# USB3_0.net
KiCad netlist of a schematic drawn in Altium Designer
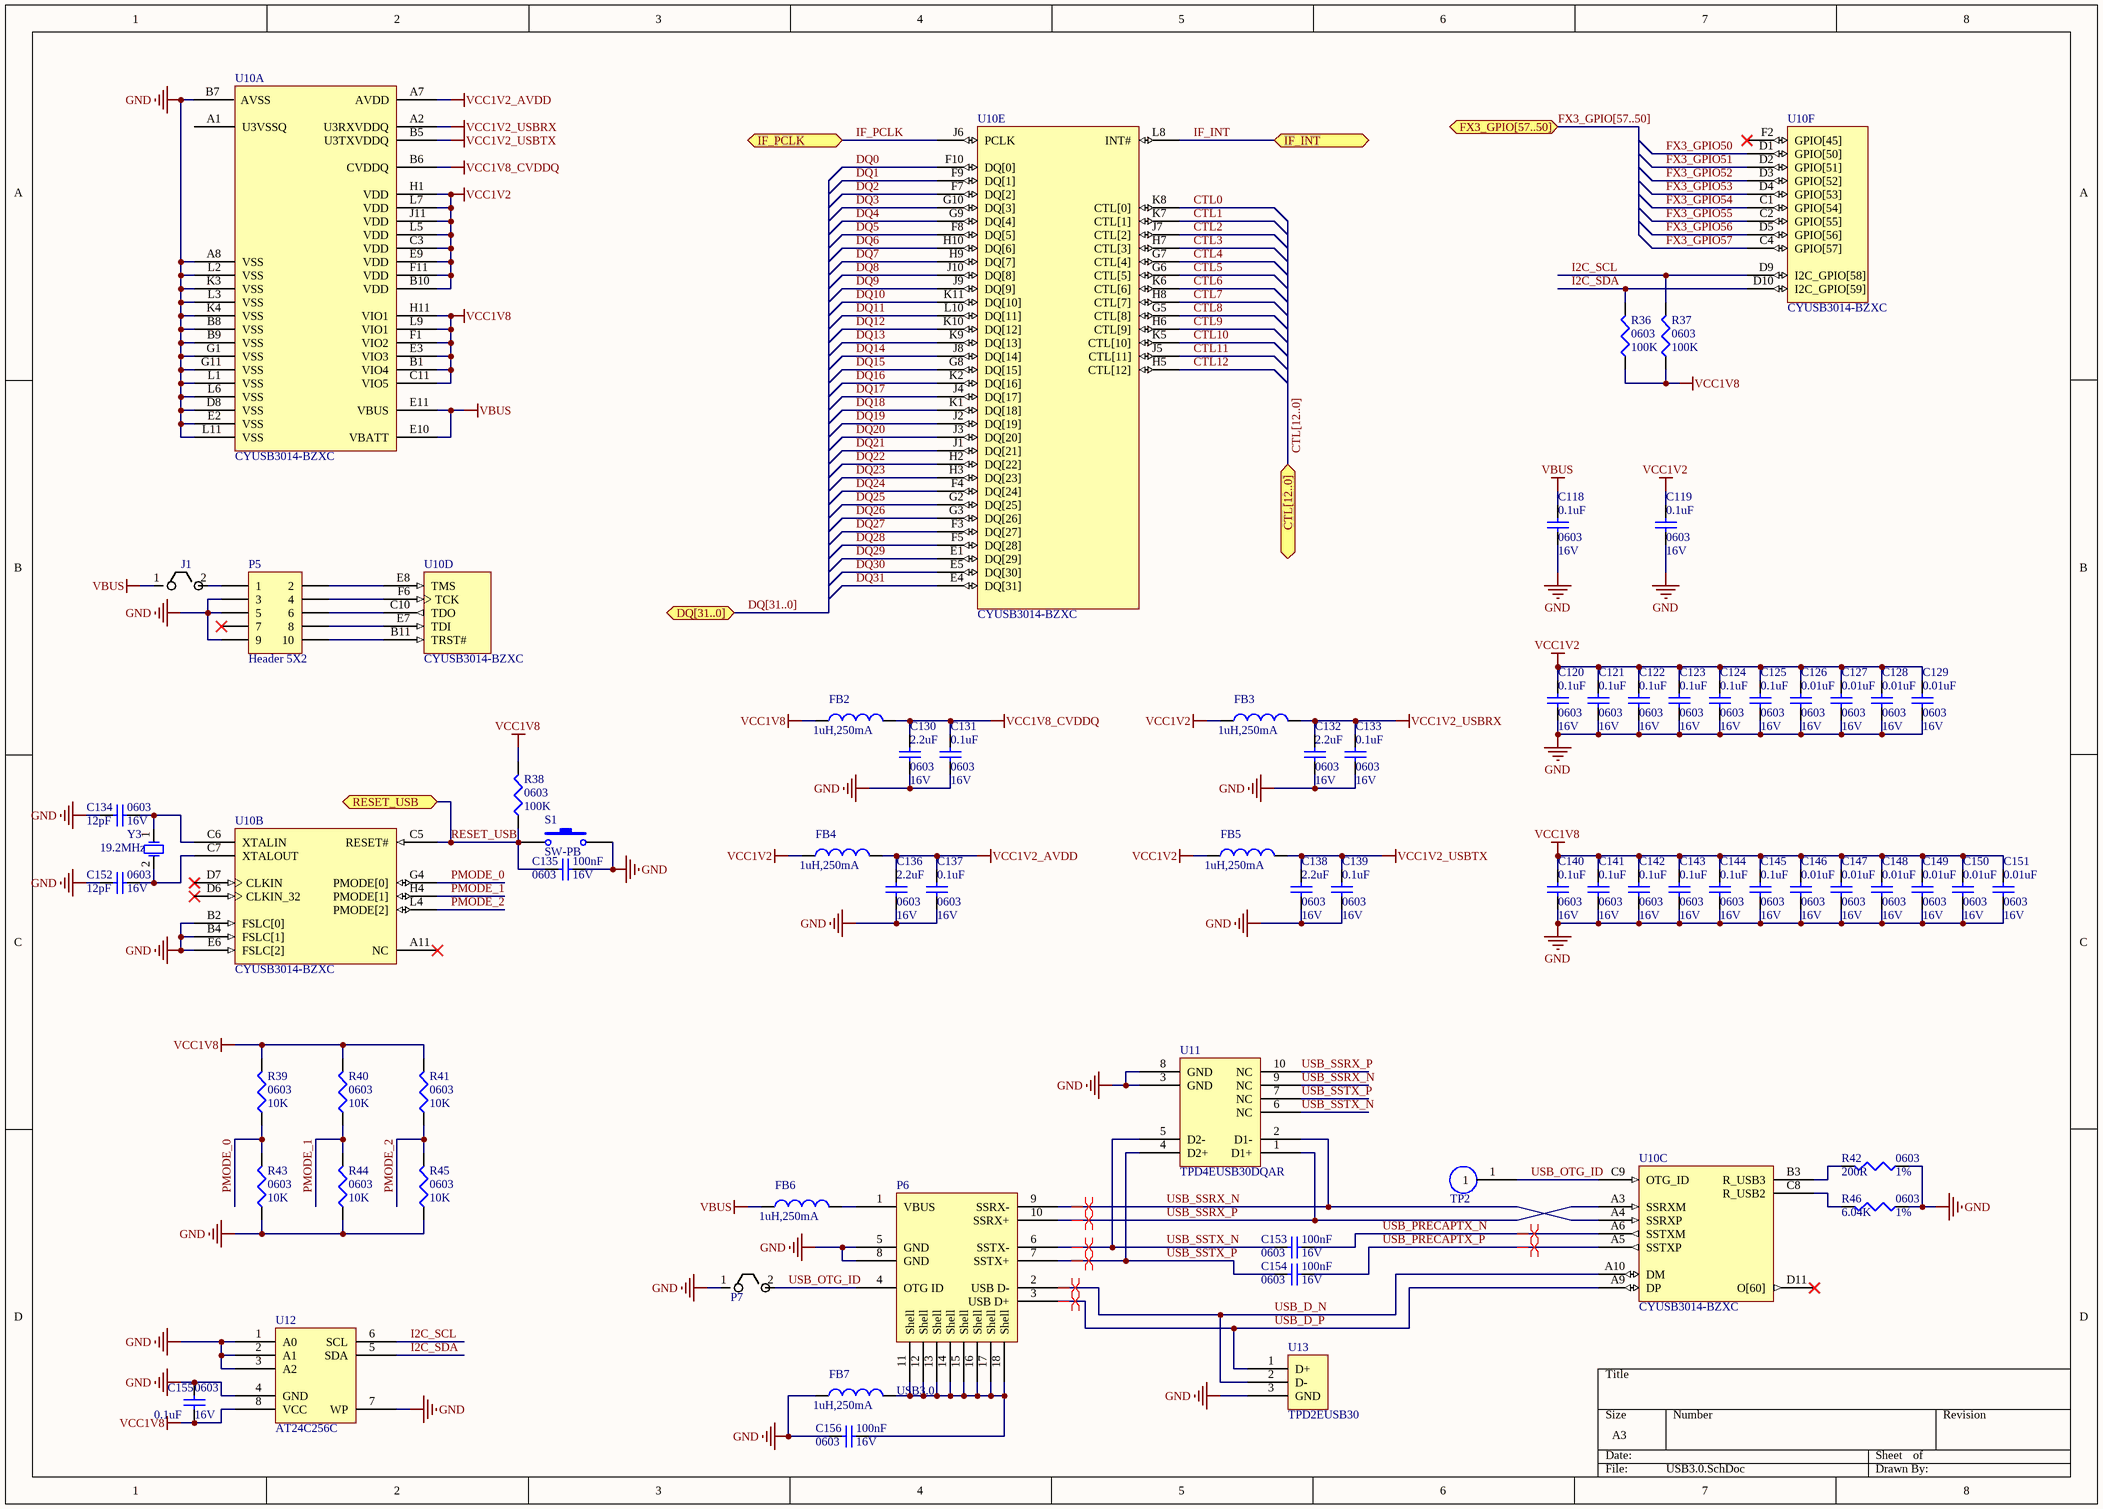
[diagram p0: USB3.0.SchDoc]

(export (version "E")
  (design (tool "Eeschema 10.0.6"))
  (components
    (comp (ref "C118")
      (value "0.1uF")
      (footprint "1608[0603]")
      (description "Capacitor (Semiconductor SIM Model)")
      (fields
        (field (name "PACKAGEREFERENCE") "0603")
        (field (name "V") "16V")
        (field (name "PUBLISHER") "Altium Limited")
      )
      (libsource (lib "Devices") (part "Cap Semi"))
    )
    (comp (ref "C119")
      (value "0.1uF")
      (footprint "1608[0603]")
      (description "Capacitor (Semiconductor SIM Model)")
      (fields
        (field (name "PACKAGEREFERENCE") "0603")
        (field (name "V") "16V")
        (field (name "PUBLISHER") "Altium Limited")
      )
      (libsource (lib "Devices") (part "Cap Semi"))
    )
    (comp (ref "C120")
      (value "0.1uF")
      (footprint "1608[0603]")
      (description "Capacitor (Semiconductor SIM Model)")
      (fields
        (field (name "PACKAGEREFERENCE") "0603")
        (field (name "V") "16V")
        (field (name "PUBLISHER") "Altium Limited")
      )
      (libsource (lib "Devices") (part "Cap Semi"))
    )
    (comp (ref "C121")
      (value "0.1uF")
      (footprint "1608[0603]")
      (description "Capacitor (Semiconductor SIM Model)")
      (fields
        (field (name "PACKAGEREFERENCE") "0603")
        (field (name "V") "16V")
        (field (name "PUBLISHER") "Altium Limited")
      )
      (libsource (lib "Devices") (part "Cap Semi"))
    )
    (comp (ref "C122")
      (value "0.1uF")
      (footprint "1608[0603]")
      (description "Capacitor (Semiconductor SIM Model)")
      (fields
        (field (name "PACKAGEREFERENCE") "0603")
        (field (name "V") "16V")
        (field (name "PUBLISHER") "Altium Limited")
      )
      (libsource (lib "Devices") (part "Cap Semi"))
    )
    (comp (ref "C123")
      (value "0.1uF")
      (footprint "1608[0603]")
      (description "Capacitor (Semiconductor SIM Model)")
      (fields
        (field (name "PACKAGEREFERENCE") "0603")
        (field (name "V") "16V")
        (field (name "PUBLISHER") "Altium Limited")
      )
      (libsource (lib "Devices") (part "Cap Semi"))
    )
    (comp (ref "C124")
      (value "0.1uF")
      (footprint "1608[0603]")
      (description "Capacitor (Semiconductor SIM Model)")
      (fields
        (field (name "PACKAGEREFERENCE") "0603")
        (field (name "V") "16V")
        (field (name "PUBLISHER") "Altium Limited")
      )
      (libsource (lib "Devices") (part "Cap Semi"))
    )
    (comp (ref "C125")
      (value "0.1uF")
      (footprint "1608[0603]")
      (description "Capacitor (Semiconductor SIM Model)")
      (fields
        (field (name "PACKAGEREFERENCE") "0603")
        (field (name "V") "16V")
        (field (name "PUBLISHER") "Altium Limited")
      )
      (libsource (lib "Devices") (part "Cap Semi"))
    )
    (comp (ref "C126")
      (value "0.01uF")
      (footprint "1608[0603]")
      (description "Capacitor (Semiconductor SIM Model)")
      (fields
        (field (name "PACKAGEREFERENCE") "0603")
        (field (name "V") "16V")
        (field (name "PUBLISHER") "Altium Limited")
      )
      (libsource (lib "Devices") (part "Cap Semi"))
    )
    (comp (ref "C127")
      (value "0.01uF")
      (footprint "1608[0603]")
      (description "Capacitor (Semiconductor SIM Model)")
      (fields
        (field (name "PACKAGEREFERENCE") "0603")
        (field (name "V") "16V")
        (field (name "PUBLISHER") "Altium Limited")
      )
      (libsource (lib "Devices") (part "Cap Semi"))
    )
    (comp (ref "C128")
      (value "0.01uF")
      (footprint "1608[0603]")
      (description "Capacitor (Semiconductor SIM Model)")
      (fields
        (field (name "PACKAGEREFERENCE") "0603")
        (field (name "V") "16V")
        (field (name "PUBLISHER") "Altium Limited")
      )
      (libsource (lib "Devices") (part "Cap Semi"))
    )
    (comp (ref "C129")
      (value "0.01uF")
      (footprint "1608[0603]")
      (description "Capacitor (Semiconductor SIM Model)")
      (fields
        (field (name "PACKAGEREFERENCE") "0603")
        (field (name "V") "16V")
        (field (name "PUBLISHER") "Altium Limited")
      )
      (libsource (lib "Devices") (part "Cap Semi"))
    )
    (comp (ref "C130")
      (value "2.2uF")
      (footprint "1608[0603]")
      (description "Capacitor (Semiconductor SIM Model)")
      (fields
        (field (name "PACKAGEREFERENCE") "0603")
        (field (name "V") "16V")
        (field (name "PUBLISHER") "Altium Limited")
      )
      (libsource (lib "Devices") (part "Cap Semi"))
    )
    (comp (ref "C131")
      (value "0.1uF")
      (footprint "1608[0603]")
      (description "Capacitor (Semiconductor SIM Model)")
      (fields
        (field (name "PACKAGEREFERENCE") "0603")
        (field (name "V") "16V")
        (field (name "PUBLISHER") "Altium Limited")
      )
      (libsource (lib "Devices") (part "Cap Semi"))
    )
    (comp (ref "C132")
      (value "2.2uF")
      (footprint "1608[0603]")
      (description "Capacitor (Semiconductor SIM Model)")
      (fields
        (field (name "PACKAGEREFERENCE") "0603")
        (field (name "V") "16V")
        (field (name "PUBLISHER") "Altium Limited")
      )
      (libsource (lib "Devices") (part "Cap Semi"))
    )
    (comp (ref "C133")
      (value "0.1uF")
      (footprint "1608[0603]")
      (description "Capacitor (Semiconductor SIM Model)")
      (fields
        (field (name "PACKAGEREFERENCE") "0603")
        (field (name "V") "16V")
        (field (name "PUBLISHER") "Altium Limited")
      )
      (libsource (lib "Devices") (part "Cap Semi"))
    )
    (comp (ref "C134")
      (value "12pF")
      (footprint "1608[0603]")
      (description "Capacitor (Semiconductor SIM Model)")
      (fields
        (field (name "PACKAGEREFERENCE") "0603")
        (field (name "V") "16V")
        (field (name "PUBLISHER") "Altium Limited")
      )
      (libsource (lib "Devices") (part "Cap Semi"))
    )
    (comp (ref "C135")
      (value "100nF")
      (footprint "1608[0603]")
      (description "Capacitor (Semiconductor SIM Model)")
      (fields
        (field (name "PACKAGEREFERENCE") "0603")
        (field (name "V") "16V")
        (field (name "PUBLISHER") "Altium Limited")
      )
      (libsource (lib "Devices") (part "Cap Semi"))
    )
    (comp (ref "C136")
      (value "2.2uF")
      (footprint "1608[0603]")
      (description "Capacitor (Semiconductor SIM Model)")
      (fields
        (field (name "PACKAGEREFERENCE") "0603")
        (field (name "V") "16V")
        (field (name "PUBLISHER") "Altium Limited")
      )
      (libsource (lib "Devices") (part "Cap Semi"))
    )
    (comp (ref "C137")
      (value "0.1uF")
      (footprint "1608[0603]")
      (description "Capacitor (Semiconductor SIM Model)")
      (fields
        (field (name "PACKAGEREFERENCE") "0603")
        (field (name "V") "16V")
        (field (name "PUBLISHER") "Altium Limited")
      )
      (libsource (lib "Devices") (part "Cap Semi"))
    )
    (comp (ref "C138")
      (value "2.2uF")
      (footprint "1608[0603]")
      (description "Capacitor (Semiconductor SIM Model)")
      (fields
        (field (name "PACKAGEREFERENCE") "0603")
        (field (name "V") "16V")
        (field (name "PUBLISHER") "Altium Limited")
      )
      (libsource (lib "Devices") (part "Cap Semi"))
    )
    (comp (ref "C139")
      (value "0.1uF")
      (footprint "1608[0603]")
      (description "Capacitor (Semiconductor SIM Model)")
      (fields
        (field (name "PACKAGEREFERENCE") "0603")
        (field (name "V") "16V")
        (field (name "PUBLISHER") "Altium Limited")
      )
      (libsource (lib "Devices") (part "Cap Semi"))
    )
    (comp (ref "C140")
      (value "0.1uF")
      (footprint "1608[0603]")
      (description "Capacitor (Semiconductor SIM Model)")
      (fields
        (field (name "PACKAGEREFERENCE") "0603")
        (field (name "V") "16V")
        (field (name "PUBLISHER") "Altium Limited")
      )
      (libsource (lib "Devices") (part "Cap Semi"))
    )
    (comp (ref "C141")
      (value "0.1uF")
      (footprint "1608[0603]")
      (description "Capacitor (Semiconductor SIM Model)")
      (fields
        (field (name "PACKAGEREFERENCE") "0603")
        (field (name "V") "16V")
        (field (name "PUBLISHER") "Altium Limited")
      )
      (libsource (lib "Devices") (part "Cap Semi"))
    )
    (comp (ref "C142")
      (value "0.1uF")
      (footprint "1608[0603]")
      (description "Capacitor (Semiconductor SIM Model)")
      (fields
        (field (name "PACKAGEREFERENCE") "0603")
        (field (name "V") "16V")
        (field (name "PUBLISHER") "Altium Limited")
      )
      (libsource (lib "Devices") (part "Cap Semi"))
    )
    (comp (ref "C143")
      (value "0.1uF")
      (footprint "1608[0603]")
      (description "Capacitor (Semiconductor SIM Model)")
      (fields
        (field (name "PACKAGEREFERENCE") "0603")
        (field (name "V") "16V")
        (field (name "PUBLISHER") "Altium Limited")
      )
      (libsource (lib "Devices") (part "Cap Semi"))
    )
    (comp (ref "C144")
      (value "0.1uF")
      (footprint "1608[0603]")
      (description "Capacitor (Semiconductor SIM Model)")
      (fields
        (field (name "PACKAGEREFERENCE") "0603")
        (field (name "V") "16V")
        (field (name "PUBLISHER") "Altium Limited")
      )
      (libsource (lib "Devices") (part "Cap Semi"))
    )
    (comp (ref "C145")
      (value "0.1uF")
      (footprint "1608[0603]")
      (description "Capacitor (Semiconductor SIM Model)")
      (fields
        (field (name "PACKAGEREFERENCE") "0603")
        (field (name "V") "16V")
        (field (name "PUBLISHER") "Altium Limited")
      )
      (libsource (lib "Devices") (part "Cap Semi"))
    )
    (comp (ref "C146")
      (value "0.01uF")
      (footprint "1608[0603]")
      (description "Capacitor (Semiconductor SIM Model)")
      (fields
        (field (name "PACKAGEREFERENCE") "0603")
        (field (name "V") "16V")
        (field (name "PUBLISHER") "Altium Limited")
      )
      (libsource (lib "Devices") (part "Cap Semi"))
    )
    (comp (ref "C147")
      (value "0.01uF")
      (footprint "1608[0603]")
      (description "Capacitor (Semiconductor SIM Model)")
      (fields
        (field (name "PACKAGEREFERENCE") "0603")
        (field (name "V") "16V")
        (field (name "PUBLISHER") "Altium Limited")
      )
      (libsource (lib "Devices") (part "Cap Semi"))
    )
    (comp (ref "C148")
      (value "0.01uF")
      (footprint "1608[0603]")
      (description "Capacitor (Semiconductor SIM Model)")
      (fields
        (field (name "PACKAGEREFERENCE") "0603")
        (field (name "V") "16V")
        (field (name "PUBLISHER") "Altium Limited")
      )
      (libsource (lib "Devices") (part "Cap Semi"))
    )
    (comp (ref "C149")
      (value "0.01uF")
      (footprint "1608[0603]")
      (description "Capacitor (Semiconductor SIM Model)")
      (fields
        (field (name "PACKAGEREFERENCE") "0603")
        (field (name "V") "16V")
        (field (name "PUBLISHER") "Altium Limited")
      )
      (libsource (lib "Devices") (part "Cap Semi"))
    )
    (comp (ref "C150")
      (value "0.01uF")
      (footprint "1608[0603]")
      (description "Capacitor (Semiconductor SIM Model)")
      (fields
        (field (name "PACKAGEREFERENCE") "0603")
        (field (name "V") "16V")
        (field (name "PUBLISHER") "Altium Limited")
      )
      (libsource (lib "Devices") (part "Cap Semi"))
    )
    (comp (ref "C151")
      (value "0.01uF")
      (footprint "1608[0603]")
      (description "Capacitor (Semiconductor SIM Model)")
      (fields
        (field (name "PACKAGEREFERENCE") "0603")
        (field (name "V") "16V")
        (field (name "PUBLISHER") "Altium Limited")
      )
      (libsource (lib "Devices") (part "Cap Semi"))
    )
    (comp (ref "C152")
      (value "12pF")
      (footprint "1608[0603]")
      (description "Capacitor (Semiconductor SIM Model)")
      (fields
        (field (name "PACKAGEREFERENCE") "0603")
        (field (name "V") "16V")
        (field (name "PUBLISHER") "Altium Limited")
      )
      (libsource (lib "Devices") (part "Cap Semi"))
    )
    (comp (ref "C153")
      (value "100nF")
      (footprint "1608[0603]")
      (description "Capacitor (Semiconductor SIM Model)")
      (fields
        (field (name "PACKAGEREFERENCE") "0603")
        (field (name "V") "16V")
        (field (name "PUBLISHER") "Altium Limited")
      )
      (libsource (lib "Devices") (part "Cap Semi"))
    )
    (comp (ref "C154")
      (value "100nF")
      (footprint "1608[0603]")
      (description "Capacitor (Semiconductor SIM Model)")
      (fields
        (field (name "PACKAGEREFERENCE") "0603")
        (field (name "V") "16V")
        (field (name "PUBLISHER") "Altium Limited")
      )
      (libsource (lib "Devices") (part "Cap Semi"))
    )
    (comp (ref "C155")
      (value "0.1uF")
      (footprint "1608[0603]")
      (description "Capacitor (Semiconductor SIM Model)")
      (fields
        (field (name "PACKAGEREFERENCE") "0603")
        (field (name "V") "16V")
        (field (name "PUBLISHER") "Altium Limited")
      )
      (libsource (lib "Devices") (part "Cap Semi"))
    )
    (comp (ref "C156")
      (value "100nF")
      (footprint "1608[0603]")
      (description "Capacitor (Semiconductor SIM Model)")
      (fields
        (field (name "PACKAGEREFERENCE") "0603")
        (field (name "V") "16V")
        (field (name "PUBLISHER") "Altium Limited")
      )
      (libsource (lib "Devices") (part "Cap Semi"))
    )
    (comp (ref "FB2")
      (value "1uH,250mA")
      (footprint "2012[0805]")
      (description "Inductor")
      (libsource (lib "Miscellaneous Devices") (part "Inductor"))
    )
    (comp (ref "FB3")
      (value "1uH,250mA")
      (footprint "2012[0805]")
      (description "Inductor")
      (libsource (lib "Miscellaneous Devices") (part "Inductor"))
    )
    (comp (ref "FB4")
      (value "1uH,250mA")
      (footprint "2012[0805]")
      (description "Inductor")
      (libsource (lib "Miscellaneous Devices") (part "Inductor"))
    )
    (comp (ref "FB5")
      (value "1uH,250mA")
      (footprint "2012[0805]")
      (description "Inductor")
      (libsource (lib "Miscellaneous Devices") (part "Inductor"))
    )
    (comp (ref "FB6")
      (value "1uH,250mA")
      (footprint "2012[0805]")
      (description "Inductor")
      (libsource (lib "Miscellaneous Devices") (part "Inductor"))
    )
    (comp (ref "FB7")
      (value "1uH,250mA")
      (footprint "2012[0805]")
      (description "Inductor")
      (libsource (lib "Miscellaneous Devices") (part "Inductor"))
    )
    (comp (ref "J1") (value "DNP") (footprint "DNP") (libsource (lib "Spartan6_LX9_A0") (part "DNP")))
    (comp (ref "P5")
      (value "Header 5X2")
      (footprint "HDR2X5")
      (description "Header, 5-Pin, Dual row")
      (fields (field (name "PUBLISHER") "Altium Limited"))
      (libsource (lib "Miscellaneous Connectors") (part "Header 5X2"))
    )
    (comp (ref "P6")
      (value "USB3.0")
      (footprint "ZX360D-B-10P")
      (libsource (lib "Spartan6_LX9_A0") (part "USB3.0"))
    )
    (comp (ref "P7") (value "DNP") (footprint "DNP") (libsource (lib "Spartan6_LX9_A0") (part "DNP")))
    (comp (ref "R36")
      (value "100K")
      (footprint "1608[0603]")
      (description "Resistor")
      (fields
        (field (name "PACKAGEREFERENCE") "0603")
        (field (name "Comment") "Res3")
        (field (name "PUBLISHER") "Altium Limited")
      )
      (libsource (lib "Miscellaneous Devices") (part "Res3"))
    )
    (comp (ref "R37")
      (value "100K")
      (footprint "1608[0603]")
      (description "Resistor")
      (fields
        (field (name "PACKAGEREFERENCE") "0603")
        (field (name "Comment") "Res3")
        (field (name "PUBLISHER") "Altium Limited")
      )
      (libsource (lib "Miscellaneous Devices") (part "Res3"))
    )
    (comp (ref "R38")
      (value "100K")
      (footprint "1608[0603]")
      (description "Resistor")
      (fields
        (field (name "PACKAGEREFERENCE") "0603")
        (field (name "Comment") "Res3")
        (field (name "PUBLISHER") "Altium Limited")
      )
      (libsource (lib "Miscellaneous Devices") (part "Res3"))
    )
    (comp (ref "R39")
      (value "10K")
      (footprint "1608[0603]")
      (description "Resistor")
      (fields
        (field (name "PACKAGEREFERENCE") "0603")
        (field (name "Comment") "Res3")
        (field (name "PUBLISHER") "Altium Limited")
      )
      (libsource (lib "Miscellaneous Devices") (part "Res3"))
    )
    (comp (ref "R40")
      (value "10K")
      (footprint "1608[0603]")
      (description "Resistor")
      (fields
        (field (name "PACKAGEREFERENCE") "0603")
        (field (name "Comment") "Res3")
        (field (name "PUBLISHER") "Altium Limited")
      )
      (libsource (lib "Miscellaneous Devices") (part "Res3"))
    )
    (comp (ref "R41")
      (value "10K")
      (footprint "1608[0603]")
      (description "Resistor")
      (fields
        (field (name "PACKAGEREFERENCE") "0603")
        (field (name "Comment") "Res3")
        (field (name "PUBLISHER") "Altium Limited")
      )
      (libsource (lib "Miscellaneous Devices") (part "Res3"))
    )
    (comp (ref "R42")
      (value "200R")
      (footprint "1608[0603]")
      (description "Resistor")
      (fields
        (field (name "PACKAGEREFERENCE") "0603")
        (field (name "AC") "1%")
        (field (name "Comment") "Res3")
        (field (name "PUBLISHER") "Altium Limited")
      )
      (libsource (lib "Miscellaneous Devices") (part "Res3"))
    )
    (comp (ref "R43")
      (value "10K")
      (footprint "1608[0603]")
      (description "Resistor")
      (fields
        (field (name "PACKAGEREFERENCE") "0603")
        (field (name "Comment") "Res3")
        (field (name "PUBLISHER") "Altium Limited")
      )
      (libsource (lib "Miscellaneous Devices") (part "Res3"))
    )
    (comp (ref "R44")
      (value "10K")
      (footprint "1608[0603]")
      (description "Resistor")
      (fields
        (field (name "PACKAGEREFERENCE") "0603")
        (field (name "Comment") "Res3")
        (field (name "PUBLISHER") "Altium Limited")
      )
      (libsource (lib "Miscellaneous Devices") (part "Res3"))
    )
    (comp (ref "R45")
      (value "10K")
      (footprint "1608[0603]")
      (description "Resistor")
      (fields
        (field (name "PACKAGEREFERENCE") "0603")
        (field (name "Comment") "Res3")
        (field (name "PUBLISHER") "Altium Limited")
      )
      (libsource (lib "Miscellaneous Devices") (part "Res3"))
    )
    (comp (ref "R46")
      (value "6.04K")
      (footprint "1608[0603]")
      (description "Resistor")
      (fields
        (field (name "PACKAGEREFERENCE") "0603")
        (field (name "AC") "1%")
        (field (name "Comment") "Res3")
        (field (name "PUBLISHER") "Altium Limited")
      )
      (libsource (lib "Miscellaneous Devices") (part "Res3"))
    )
    (comp (ref "S1")
      (value "SW-PB")
      (footprint "SPST-2")
      (description "Switch")
      (fields (field (name "PUBLISHER") "Altium Limited"))
      (libsource (lib "Miscellaneous Devices") (part "SW-PB"))
    )
    (comp (ref "TP2") (value "TP") (libsource (lib "Spartan6_LX9_A0") (part "TP")))
    (comp (ref "U10")
      (value "CYUSB3014-BZXC")
      (footprint "CYUSB3014")
      (libsource (lib "Spartan6_LX9_A0") (part "CYUSB3014-BZXC"))
    )
    (comp (ref "U11")
      (value "TPD4EUSB30DQAR")
      (footprint "TPD4EUSB30")
      (description "4-Channel ESD Protection for Super-Speed USB 3.0 Interface")
      (libsource (lib "Spartan6_LX9_A0") (part "TPD4EUSB30DQAR"))
    )
    (comp (ref "U12")
      (value "AT24C256C")
      (footprint "AT24C256C[SOP8]")
      (libsource (lib "Spartan6_LX9_A0") (part "AT24C256C"))
    )
    (comp (ref "U13")
      (value "TPD2EUSB30")
      (footprint "TPE2USB30")
      (libsource (lib "Spartan6_LX9_A0") (part "TPD2EUSB30"))
    )
    (comp (ref "Y3")
      (value "19.2MHz")
      (footprint "XTAL_A")
      (description "Crystal Oscillator")
      (fields (field (name "PUBLISHER") "Altium Limited"))
      (libsource (lib "Devices") (part "XTAL"))
    )
  )
  (nets
    (net (code "1") (name "/CTL0") (class "Default")
      (node (ref "U10") (pin "K8") (pinfunction "CTL[0]_K8") (pintype "bidirectional"))
    )
    (net (code "2") (name "/CTL1") (class "Default")
      (node (ref "U10") (pin "K7") (pinfunction "CTL[1]_K7") (pintype "bidirectional"))
    )
    (net (code "3") (name "/CTL2") (class "Default")
      (node (ref "U10") (pin "J7") (pinfunction "CTL[2]_J7") (pintype "bidirectional"))
    )
    (net (code "4") (name "/CTL3") (class "Default")
      (node (ref "U10") (pin "H7") (pinfunction "CTL[3]_H7") (pintype "bidirectional"))
    )
    (net (code "5") (name "/CTL4") (class "Default")
      (node (ref "U10") (pin "G7") (pinfunction "CTL[4]_G7") (pintype "bidirectional"))
    )
    (net (code "6") (name "/CTL5") (class "Default")
      (node (ref "U10") (pin "G6") (pinfunction "CTL[5]_G6") (pintype "bidirectional"))
    )
    (net (code "7") (name "/CTL6") (class "Default")
      (node (ref "U10") (pin "K6") (pinfunction "CTL[6]_K6") (pintype "bidirectional"))
    )
    (net (code "8") (name "/CTL7") (class "Default")
      (node (ref "U10") (pin "H8") (pinfunction "CTL[7]_H8") (pintype "bidirectional"))
    )
    (net (code "9") (name "/CTL8") (class "Default")
      (node (ref "U10") (pin "G5") (pinfunction "CTL[8]_G5") (pintype "bidirectional"))
    )
    (net (code "10") (name "/CTL9") (class "Default")
      (node (ref "U10") (pin "H6") (pinfunction "CTL[9]_H6") (pintype "bidirectional"))
    )
    (net (code "11") (name "/CTL10") (class "Default")
      (node (ref "U10") (pin "K5") (pinfunction "CTL[10]_K5") (pintype "bidirectional"))
    )
    (net (code "12") (name "/CTL11") (class "Default")
      (node (ref "U10") (pin "J5") (pinfunction "CTL[11]_J5") (pintype "bidirectional"))
    )
    (net (code "13") (name "/CTL12") (class "Default")
      (node (ref "U10") (pin "H5") (pinfunction "CTL[12]_H5") (pintype "bidirectional"))
    )
    (net (code "15") (name "/DQ0") (class "Default")
      (node (ref "U10") (pin "F10") (pinfunction "DQ[0]_F10") (pintype "bidirectional"))
    )
    (net (code "16") (name "/DQ1") (class "Default")
      (node (ref "U10") (pin "F9") (pinfunction "DQ[1]_F9") (pintype "bidirectional"))
    )
    (net (code "17") (name "/DQ2") (class "Default")
      (node (ref "U10") (pin "F7") (pinfunction "DQ[2]_F7") (pintype "bidirectional"))
    )
    (net (code "18") (name "/DQ3") (class "Default")
      (node (ref "U10") (pin "G10") (pinfunction "DQ[3]_G10") (pintype "bidirectional"))
    )
    (net (code "19") (name "/DQ4") (class "Default")
      (node (ref "U10") (pin "G9") (pinfunction "DQ[4]_G9") (pintype "bidirectional"))
    )
    (net (code "20") (name "/DQ5") (class "Default")
      (node (ref "U10") (pin "F8") (pinfunction "DQ[5]_F8") (pintype "bidirectional"))
    )
    (net (code "21") (name "/DQ6") (class "Default")
      (node (ref "U10") (pin "H10") (pinfunction "DQ[6]_H10") (pintype "bidirectional"))
    )
    (net (code "22") (name "/DQ7") (class "Default")
      (node (ref "U10") (pin "H9") (pinfunction "DQ[7]_H9") (pintype "bidirectional"))
    )
    (net (code "23") (name "/DQ8") (class "Default")
      (node (ref "U10") (pin "J10") (pinfunction "DQ[8]_J10") (pintype "bidirectional"))
    )
    (net (code "24") (name "/DQ9") (class "Default")
      (node (ref "U10") (pin "J9") (pinfunction "DQ[9]_J9") (pintype "bidirectional"))
    )
    (net (code "25") (name "/DQ10") (class "Default")
      (node (ref "U10") (pin "K11") (pinfunction "DQ[10]_K11") (pintype "bidirectional"))
    )
    (net (code "26") (name "/DQ11") (class "Default")
      (node (ref "U10") (pin "L10") (pinfunction "DQ[11]_L10") (pintype "bidirectional"))
    )
    (net (code "27") (name "/DQ12") (class "Default")
      (node (ref "U10") (pin "K10") (pinfunction "DQ[12]_K10") (pintype "bidirectional"))
    )
    (net (code "28") (name "/DQ13") (class "Default")
      (node (ref "U10") (pin "K9") (pinfunction "DQ[13]_K9") (pintype "bidirectional"))
    )
    (net (code "29") (name "/DQ14") (class "Default")
      (node (ref "U10") (pin "J8") (pinfunction "DQ[14]_J8") (pintype "bidirectional"))
    )
    (net (code "30") (name "/DQ15") (class "Default")
      (node (ref "U10") (pin "G8") (pinfunction "DQ[15]_G8") (pintype "bidirectional"))
    )
    (net (code "31") (name "/DQ16") (class "Default")
      (node (ref "U10") (pin "K2") (pinfunction "DQ[16]_K2") (pintype "bidirectional"))
    )
    (net (code "32") (name "/DQ17") (class "Default")
      (node (ref "U10") (pin "J4") (pinfunction "DQ[17]_J4") (pintype "bidirectional"))
    )
    (net (code "33") (name "/DQ18") (class "Default")
      (node (ref "U10") (pin "K1") (pinfunction "DQ[18]_K1") (pintype "bidirectional"))
    )
    (net (code "34") (name "/DQ19") (class "Default")
      (node (ref "U10") (pin "J2") (pinfunction "DQ[19]_J2") (pintype "bidirectional"))
    )
    (net (code "35") (name "/DQ20") (class "Default")
      (node (ref "U10") (pin "J3") (pinfunction "DQ[20]_J3") (pintype "bidirectional"))
    )
    (net (code "36") (name "/DQ21") (class "Default")
      (node (ref "U10") (pin "J1") (pinfunction "DQ[21]_J1") (pintype "bidirectional"))
    )
    (net (code "37") (name "/DQ22") (class "Default")
      (node (ref "U10") (pin "H2") (pinfunction "DQ[22]_H2") (pintype "bidirectional"))
    )
    (net (code "38") (name "/DQ23") (class "Default")
      (node (ref "U10") (pin "H3") (pinfunction "DQ[23]_H3") (pintype "bidirectional"))
    )
    (net (code "39") (name "/DQ24") (class "Default")
      (node (ref "U10") (pin "F4") (pinfunction "DQ[24]_F4") (pintype "bidirectional"))
    )
    (net (code "40") (name "/DQ25") (class "Default")
      (node (ref "U10") (pin "G2") (pinfunction "DQ[25]_G2") (pintype "bidirectional"))
    )
    (net (code "41") (name "/DQ26") (class "Default")
      (node (ref "U10") (pin "G3") (pinfunction "DQ[26]_G3") (pintype "bidirectional"))
    )
    (net (code "42") (name "/DQ27") (class "Default")
      (node (ref "U10") (pin "F3") (pinfunction "DQ[27]_F3") (pintype "bidirectional"))
    )
    (net (code "43") (name "/DQ28") (class "Default")
      (node (ref "U10") (pin "F5") (pinfunction "DQ[28]_F5") (pintype "bidirectional"))
    )
    (net (code "44") (name "/DQ29") (class "Default")
      (node (ref "U10") (pin "E1") (pinfunction "DQ[29]_E1") (pintype "bidirectional"))
    )
    (net (code "45") (name "/DQ30") (class "Default")
      (node (ref "U10") (pin "E5") (pinfunction "DQ[30]_E5") (pintype "bidirectional"))
    )
    (net (code "46") (name "/DQ31") (class "Default")
      (node (ref "U10") (pin "E4") (pinfunction "DQ[31]_E4") (pintype "bidirectional"))
    )
    (net (code "48") (name "/FX3_GPIO50") (class "Default")
      (node (ref "U10") (pin "D1") (pinfunction "GPIO[50]_D1") (pintype "bidirectional"))
    )
    (net (code "49") (name "/FX3_GPIO51") (class "Default")
      (node (ref "U10") (pin "D2") (pinfunction "GPIO[51]_D2") (pintype "bidirectional"))
    )
    (net (code "50") (name "/FX3_GPIO52") (class "Default")
      (node (ref "U10") (pin "D3") (pinfunction "GPIO[52]_D3") (pintype "bidirectional"))
    )
    (net (code "51") (name "/FX3_GPIO53") (class "Default")
      (node (ref "U10") (pin "D4") (pinfunction "GPIO[53]_D4") (pintype "bidirectional"))
    )
    (net (code "52") (name "/FX3_GPIO54") (class "Default")
      (node (ref "U10") (pin "C1") (pinfunction "GPIO[54]_C1") (pintype "bidirectional"))
    )
    (net (code "53") (name "/FX3_GPIO55") (class "Default")
      (node (ref "U10") (pin "C2") (pinfunction "GPIO[55]_C2") (pintype "bidirectional"))
    )
    (net (code "54") (name "/FX3_GPIO56") (class "Default")
      (node (ref "U10") (pin "D5") (pinfunction "GPIO[56]_D5") (pintype "bidirectional"))
    )
    (net (code "55") (name "/FX3_GPIO57") (class "Default")
      (node (ref "U10") (pin "C4") (pinfunction "GPIO[57]_C4") (pintype "bidirectional"))
    )
    (net (code "57") (name "/I2C_SCL") (class "Default")
      (node (ref "R37") (pin "2") (pinfunction "2_2") (pintype "passive"))
      (node (ref "U10") (pin "D9") (pinfunction "I2C_GPIO[58]_D9") (pintype "bidirectional"))
      (node (ref "U12") (pin "6") (pinfunction "SCL_6") (pintype "passive"))
    )
    (net (code "58") (name "/I2C_SDA") (class "Default")
      (node (ref "R36") (pin "2") (pinfunction "2_2") (pintype "passive"))
      (node (ref "U10") (pin "D10") (pinfunction "I2C_GPIO[59]_D10") (pintype "bidirectional"))
      (node (ref "U12") (pin "5") (pinfunction "SDA_5") (pintype "passive"))
    )
    (net (code "59") (name "/IF_INT") (class "Default")
      (node (ref "U10") (pin "L8") (pinfunction "INT#_L8") (pintype "bidirectional"))
    )
    (net (code "60") (name "/IF_PCLK") (class "Default")
      (node (ref "U10") (pin "J6") (pinfunction "PCLK_J6") (pintype "bidirectional"))
    )
    (net (code "61") (name "/PMODE_0") (class "Default")
      (node (ref "R39") (pin "1") (pinfunction "1_1") (pintype "passive"))
      (node (ref "R43") (pin "2") (pinfunction "2_2") (pintype "passive"))
      (node (ref "U10") (pin "G4") (pinfunction "PMODE[0]_G4") (pintype "bidirectional"))
    )
    (net (code "62") (name "/PMODE_1") (class "Default")
      (node (ref "R40") (pin "1") (pinfunction "1_1") (pintype "passive"))
      (node (ref "R44") (pin "2") (pinfunction "2_2") (pintype "passive"))
      (node (ref "U10") (pin "H4") (pinfunction "PMODE[1]_H4") (pintype "bidirectional"))
    )
    (net (code "63") (name "/PMODE_2") (class "Default")
      (node (ref "R41") (pin "1") (pinfunction "1_1") (pintype "passive"))
      (node (ref "R45") (pin "2") (pinfunction "2_2") (pintype "passive"))
      (node (ref "U10") (pin "L4") (pinfunction "PMODE[2]_L4") (pintype "bidirectional"))
    )
    (net (code "64") (name "/RESET_USB") (class "Default")
      (node (ref "C135") (pin "1") (pinfunction "1_1") (pintype "passive"))
      (node (ref "R38") (pin "1") (pinfunction "1_1") (pintype "passive"))
      (node (ref "S1") (pin "1") (pinfunction "1_1") (pintype "passive"))
      (node (ref "U10") (pin "C5") (pinfunction "RESET#_C5") (pintype "input"))
    )
    (net (code "65") (name "/USB_D_N") (class "Default")
      (node (ref "P6") (pin "2") (pinfunction "USB_D-_2") (pintype "passive"))
      (node (ref "U10") (pin "A10") (pinfunction "DM_A10") (pintype "bidirectional"))
      (node (ref "U13") (pin "2") (pinfunction "D-_2") (pintype "passive"))
    )
    (net (code "66") (name "/USB_D_P") (class "Default")
      (node (ref "P6") (pin "3") (pinfunction "USB_D+_3") (pintype "passive"))
      (node (ref "U10") (pin "A9") (pinfunction "DP_A9") (pintype "bidirectional"))
      (node (ref "U13") (pin "1") (pinfunction "D+_1") (pintype "passive"))
    )
    (net (code "67") (name "/USB_OTG_ID") (class "Default")
      (node (ref "P6") (pin "4") (pinfunction "OTG_ID_4") (pintype "passive"))
      (node (ref "P7") (pin "2") (pinfunction "2_2") (pintype "passive"))
      (node (ref "TP2") (pin "1") (pinfunction "1_1") (pintype "passive"))
      (node (ref "U10") (pin "C9") (pinfunction "OTG_ID_C9") (pintype "input"))
    )
    (net (code "68") (name "/USB_PRECAPTX_N") (class "Default")
      (node (ref "C153") (pin "2") (pinfunction "2_2") (pintype "passive"))
      (node (ref "U10") (pin "A6") (pinfunction "SSTXM_A6") (pintype "output"))
    )
    (net (code "69") (name "/USB_PRECAPTX_P") (class "Default")
      (node (ref "C154") (pin "2") (pinfunction "2_2") (pintype "passive"))
      (node (ref "U10") (pin "A5") (pinfunction "SSTXP_A5") (pintype "output"))
    )
    (net (code "70") (name "/USB_SSRX_N") (class "Default")
      (node (ref "P6") (pin "9") (pinfunction "SSRX-_9") (pintype "passive"))
      (node (ref "U10") (pin "A4") (pinfunction "SSRXP_A4") (pintype "input"))
      (node (ref "U11") (pin "2") (pinfunction "D1-_2") (pintype "passive"))
      (node (ref "U11") (pin "9") (pinfunction "NC_9") (pintype "passive"))
    )
    (net (code "71") (name "/USB_SSRX_P") (class "Default")
      (node (ref "P6") (pin "10") (pinfunction "SSRX+_10") (pintype "passive"))
      (node (ref "U10") (pin "A3") (pinfunction "SSRXM_A3") (pintype "input"))
      (node (ref "U11") (pin "1") (pinfunction "D1+_1") (pintype "passive"))
      (node (ref "U11") (pin "10") (pinfunction "NC_10") (pintype "passive"))
    )
    (net (code "72") (name "/USB_SSTX_N") (class "Default")
      (node (ref "C153") (pin "1") (pinfunction "1_1") (pintype "passive"))
      (node (ref "P6") (pin "6") (pinfunction "SSTX-_6") (pintype "passive"))
      (node (ref "U11") (pin "5") (pinfunction "D2-_5") (pintype "passive"))
      (node (ref "U11") (pin "6") (pinfunction "NC_6") (pintype "passive"))
    )
    (net (code "73") (name "/USB_SSTX_P") (class "Default")
      (node (ref "C154") (pin "1") (pinfunction "1_1") (pintype "passive"))
      (node (ref "P6") (pin "7") (pinfunction "SSTX+_7") (pintype "passive"))
      (node (ref "U11") (pin "4") (pinfunction "D2+_4") (pintype "passive"))
      (node (ref "U11") (pin "7") (pinfunction "NC_7") (pintype "passive"))
    )
    (net (code "74") (name "GND") (class "Default")
      (node (ref "C118") (pin "2") (pinfunction "2_2") (pintype "passive"))
      (node (ref "C119") (pin "2") (pinfunction "2_2") (pintype "passive"))
      (node (ref "C120") (pin "2") (pinfunction "2_2") (pintype "passive"))
      (node (ref "C121") (pin "2") (pinfunction "2_2") (pintype "passive"))
      (node (ref "C122") (pin "2") (pinfunction "2_2") (pintype "passive"))
      (node (ref "C123") (pin "2") (pinfunction "2_2") (pintype "passive"))
      (node (ref "C124") (pin "2") (pinfunction "2_2") (pintype "passive"))
      (node (ref "C125") (pin "2") (pinfunction "2_2") (pintype "passive"))
      (node (ref "C126") (pin "2") (pinfunction "2_2") (pintype "passive"))
      (node (ref "C127") (pin "2") (pinfunction "2_2") (pintype "passive"))
      (node (ref "C128") (pin "2") (pinfunction "2_2") (pintype "passive"))
      (node (ref "C129") (pin "2") (pinfunction "2_2") (pintype "passive"))
      (node (ref "C130") (pin "2") (pinfunction "2_2") (pintype "passive"))
      (node (ref "C131") (pin "2") (pinfunction "2_2") (pintype "passive"))
      (node (ref "C132") (pin "2") (pinfunction "2_2") (pintype "passive"))
      (node (ref "C133") (pin "2") (pinfunction "2_2") (pintype "passive"))
      (node (ref "C134") (pin "2") (pinfunction "2_2") (pintype "passive"))
      (node (ref "C135") (pin "2") (pinfunction "2_2") (pintype "passive"))
      (node (ref "C136") (pin "2") (pinfunction "2_2") (pintype "passive"))
      (node (ref "C137") (pin "2") (pinfunction "2_2") (pintype "passive"))
      (node (ref "C138") (pin "2") (pinfunction "2_2") (pintype "passive"))
      (node (ref "C139") (pin "2") (pinfunction "2_2") (pintype "passive"))
      (node (ref "C140") (pin "2") (pinfunction "2_2") (pintype "passive"))
      (node (ref "C141") (pin "2") (pinfunction "2_2") (pintype "passive"))
      (node (ref "C142") (pin "2") (pinfunction "2_2") (pintype "passive"))
      (node (ref "C143") (pin "2") (pinfunction "2_2") (pintype "passive"))
      (node (ref "C144") (pin "2") (pinfunction "2_2") (pintype "passive"))
      (node (ref "C145") (pin "2") (pinfunction "2_2") (pintype "passive"))
      (node (ref "C146") (pin "2") (pinfunction "2_2") (pintype "passive"))
      (node (ref "C147") (pin "2") (pinfunction "2_2") (pintype "passive"))
      (node (ref "C148") (pin "2") (pinfunction "2_2") (pintype "passive"))
      (node (ref "C149") (pin "2") (pinfunction "2_2") (pintype "passive"))
      (node (ref "C150") (pin "2") (pinfunction "2_2") (pintype "passive"))
      (node (ref "C151") (pin "2") (pinfunction "2_2") (pintype "passive"))
      (node (ref "C152") (pin "2") (pinfunction "2_2") (pintype "passive"))
      (node (ref "C155") (pin "2") (pinfunction "2_2") (pintype "passive"))
      (node (ref "C156") (pin "1") (pinfunction "1_1") (pintype "passive"))
      (node (ref "FB7") (pin "1") (pinfunction "1_1") (pintype "passive"))
      (node (ref "P5") (pin "3") (pinfunction "3_3") (pintype "passive"))
      (node (ref "P5") (pin "5") (pinfunction "5_5") (pintype "passive"))
      (node (ref "P5") (pin "9") (pinfunction "9_9") (pintype "passive"))
      (node (ref "P6") (pin "5") (pinfunction "GND_5") (pintype "passive"))
      (node (ref "P6") (pin "8") (pinfunction "GND_8") (pintype "passive"))
      (node (ref "P7") (pin "1") (pinfunction "1_1") (pintype "passive"))
      (node (ref "R42") (pin "1") (pinfunction "1_1") (pintype "passive"))
      (node (ref "R43") (pin "1") (pinfunction "1_1") (pintype "passive"))
      (node (ref "R44") (pin "1") (pinfunction "1_1") (pintype "passive"))
      (node (ref "R45") (pin "1") (pinfunction "1_1") (pintype "passive"))
      (node (ref "R46") (pin "1") (pinfunction "1_1") (pintype "passive"))
      (node (ref "S1") (pin "2") (pinfunction "2_2") (pintype "passive"))
      (node (ref "U10") (pin "A8") (pinfunction "VSS_A8") (pintype "power_in"))
      (node (ref "U10") (pin "B2") (pinfunction "FSLC[0]_B2") (pintype "input"))
      (node (ref "U10") (pin "B4") (pinfunction "FSLC[1]_B4") (pintype "input"))
      (node (ref "U10") (pin "B7") (pinfunction "AVSS_B7") (pintype "power_in"))
      (node (ref "U10") (pin "B8") (pinfunction "VSS_B8") (pintype "power_in"))
      (node (ref "U10") (pin "B9") (pinfunction "VSS_B9") (pintype "power_in"))
      (node (ref "U10") (pin "D8") (pinfunction "VSS_D8") (pintype "power_in"))
      (node (ref "U10") (pin "E2") (pinfunction "VSS_E2") (pintype "power_in"))
      (node (ref "U10") (pin "E6") (pinfunction "FSLC[2]_E6") (pintype "input"))
      (node (ref "U10") (pin "G1") (pinfunction "VSS_G1") (pintype "power_in"))
      (node (ref "U10") (pin "G11") (pinfunction "VSS_G11") (pintype "power_in"))
      (node (ref "U10") (pin "K3") (pinfunction "VSS_K3") (pintype "power_in"))
      (node (ref "U10") (pin "K4") (pinfunction "VSS_K4") (pintype "power_in"))
      (node (ref "U10") (pin "L1") (pinfunction "VSS_L1") (pintype "power_in"))
      (node (ref "U10") (pin "L11") (pinfunction "VSS_L11") (pintype "power_in"))
      (node (ref "U10") (pin "L2") (pinfunction "VSS_L2") (pintype "power_in"))
      (node (ref "U10") (pin "L3") (pinfunction "VSS_L3") (pintype "power_in"))
      (node (ref "U10") (pin "L6") (pinfunction "VSS_L6") (pintype "power_in"))
      (node (ref "U11") (pin "3") (pinfunction "GND_3") (pintype "passive"))
      (node (ref "U11") (pin "8") (pinfunction "GND_8") (pintype "passive"))
      (node (ref "U12") (pin "1") (pinfunction "A0_1") (pintype "passive"))
      (node (ref "U12") (pin "2") (pinfunction "A1_2") (pintype "passive"))
      (node (ref "U12") (pin "3") (pinfunction "A2_3") (pintype "passive"))
      (node (ref "U12") (pin "4") (pinfunction "GND_4") (pintype "passive"))
      (node (ref "U12") (pin "7") (pinfunction "WP_7") (pintype "passive"))
      (node (ref "U13") (pin "3") (pinfunction "GND_3") (pintype "passive"))
    )
    (net (code "75") (name "Net-(C156-Pad2)") (class "Default")
      (node (ref "C156") (pin "2") (pinfunction "2_2") (pintype "passive"))
      (node (ref "FB7") (pin "2") (pinfunction "2_2") (pintype "passive"))
      (node (ref "P6") (pin "11") (pinfunction "Shell_11") (pintype "passive"))
      (node (ref "P6") (pin "12") (pinfunction "Shell_12") (pintype "passive"))
      (node (ref "P6") (pin "13") (pinfunction "Shell_13") (pintype "passive"))
      (node (ref "P6") (pin "14") (pinfunction "Shell_14") (pintype "passive"))
      (node (ref "P6") (pin "15") (pinfunction "Shell_15") (pintype "passive"))
      (node (ref "P6") (pin "16") (pinfunction "Shell_16") (pintype "passive"))
      (node (ref "P6") (pin "17") (pinfunction "Shell_17") (pintype "passive"))
      (node (ref "P6") (pin "18") (pinfunction "Shell_18") (pintype "passive"))
    )
    (net (code "76") (name "Net-(J1-Pad2)") (class "Default")
      (node (ref "J1") (pin "2") (pinfunction "2_2") (pintype "passive"))
      (node (ref "P5") (pin "1") (pinfunction "1_1") (pintype "passive"))
    )
    (net (code "77") (name "Net-(P6-VBUS)") (class "Default")
      (node (ref "FB6") (pin "2") (pinfunction "2_2") (pintype "passive"))
      (node (ref "P6") (pin "1") (pinfunction "VBUS_1") (pintype "passive"))
    )
    (net (code "78") (name "Net-(U10B-XTALIN)") (class "Default")
      (node (ref "C134") (pin "1") (pinfunction "1_1") (pintype "passive"))
      (node (ref "U10") (pin "C6") (pinfunction "XTALIN_C6") (pintype "passive"))
      (node (ref "Y3") (pin "1") (pinfunction "OSC1_1") (pintype "passive"))
    )
    (net (code "79") (name "Net-(U10B-XTALOUT)") (class "Default")
      (node (ref "C152") (pin "1") (pinfunction "1_1") (pintype "passive"))
      (node (ref "U10") (pin "C7") (pinfunction "XTALOUT_C7") (pintype "passive"))
      (node (ref "Y3") (pin "2") (pinfunction "OSC2_2") (pintype "passive"))
    )
    (net (code "80") (name "Net-(U10C-R_USB2)") (class "Default")
      (node (ref "R46") (pin "2") (pinfunction "2_2") (pintype "passive"))
      (node (ref "U10") (pin "C8") (pinfunction "R_USB2_C8") (pintype "passive"))
    )
    (net (code "81") (name "Net-(U10C-R_USB3)") (class "Default")
      (node (ref "R42") (pin "2") (pinfunction "2_2") (pintype "passive"))
      (node (ref "U10") (pin "B3") (pinfunction "R_USB3_B3") (pintype "passive"))
    )
    (net (code "82") (name "Net-(U10D-TCK)") (class "Default")
      (node (ref "P5") (pin "4") (pinfunction "4_4") (pintype "passive"))
      (node (ref "U10") (pin "F6") (pinfunction "TCK_F6") (pintype "input"))
    )
    (net (code "83") (name "Net-(U10D-TDI)") (class "Default")
      (node (ref "P5") (pin "8") (pinfunction "8_8") (pintype "passive"))
      (node (ref "U10") (pin "E7") (pinfunction "TDI_E7") (pintype "input"))
    )
    (net (code "84") (name "Net-(U10D-TDO)") (class "Default")
      (node (ref "P5") (pin "6") (pinfunction "6_6") (pintype "passive"))
      (node (ref "U10") (pin "C10") (pinfunction "TDO_C10") (pintype "output"))
    )
    (net (code "85") (name "Net-(U10D-TMS)") (class "Default")
      (node (ref "P5") (pin "2") (pinfunction "2_2") (pintype "passive"))
      (node (ref "U10") (pin "E8") (pinfunction "TMS_E8") (pintype "input"))
    )
    (net (code "86") (name "Net-(U10D-TRST#)") (class "Default")
      (node (ref "P5") (pin "10") (pinfunction "10_10") (pintype "passive"))
      (node (ref "U10") (pin "B11") (pinfunction "TRST#_B11") (pintype "input"))
    )
    (net (code "87") (name "VBUS") (class "Default")
      (node (ref "C118") (pin "1") (pinfunction "1_1") (pintype "passive"))
      (node (ref "FB6") (pin "1") (pinfunction "1_1") (pintype "passive"))
      (node (ref "J1") (pin "1") (pinfunction "1_1") (pintype "passive"))
      (node (ref "U10") (pin "E10") (pinfunction "VBATT_E10") (pintype "power_in"))
      (node (ref "U10") (pin "E11") (pinfunction "VBUS_E11") (pintype "power_in"))
    )
    (net (code "88") (name "VCC1V2") (class "Default")
      (node (ref "C119") (pin "1") (pinfunction "1_1") (pintype "passive"))
      (node (ref "C120") (pin "1") (pinfunction "1_1") (pintype "passive"))
      (node (ref "C121") (pin "1") (pinfunction "1_1") (pintype "passive"))
      (node (ref "C122") (pin "1") (pinfunction "1_1") (pintype "passive"))
      (node (ref "C123") (pin "1") (pinfunction "1_1") (pintype "passive"))
      (node (ref "C124") (pin "1") (pinfunction "1_1") (pintype "passive"))
      (node (ref "C125") (pin "1") (pinfunction "1_1") (pintype "passive"))
      (node (ref "C126") (pin "1") (pinfunction "1_1") (pintype "passive"))
      (node (ref "C127") (pin "1") (pinfunction "1_1") (pintype "passive"))
      (node (ref "C128") (pin "1") (pinfunction "1_1") (pintype "passive"))
      (node (ref "C129") (pin "1") (pinfunction "1_1") (pintype "passive"))
      (node (ref "FB3") (pin "1") (pinfunction "1_1") (pintype "passive"))
      (node (ref "FB4") (pin "1") (pinfunction "1_1") (pintype "passive"))
      (node (ref "FB5") (pin "1") (pinfunction "1_1") (pintype "passive"))
      (node (ref "U10") (pin "B10") (pinfunction "VDD_B10") (pintype "power_in"))
      (node (ref "U10") (pin "C3") (pinfunction "VDD_C3") (pintype "power_in"))
      (node (ref "U10") (pin "E9") (pinfunction "VDD_E9") (pintype "power_in"))
      (node (ref "U10") (pin "F11") (pinfunction "VDD_F11") (pintype "power_in"))
      (node (ref "U10") (pin "H1") (pinfunction "VDD_H1") (pintype "power_in"))
      (node (ref "U10") (pin "J11") (pinfunction "VDD_J11") (pintype "power_in"))
      (node (ref "U10") (pin "L5") (pinfunction "VDD_L5") (pintype "power_in"))
      (node (ref "U10") (pin "L7") (pinfunction "VDD_L7") (pintype "power_in"))
    )
    (net (code "89") (name "VCC1V2_AVDD") (class "Default")
      (node (ref "C136") (pin "1") (pinfunction "1_1") (pintype "passive"))
      (node (ref "C137") (pin "1") (pinfunction "1_1") (pintype "passive"))
      (node (ref "FB4") (pin "2") (pinfunction "2_2") (pintype "passive"))
      (node (ref "U10") (pin "A7") (pinfunction "AVDD_A7") (pintype "power_in"))
    )
    (net (code "90") (name "VCC1V2_USBRX") (class "Default")
      (node (ref "C132") (pin "1") (pinfunction "1_1") (pintype "passive"))
      (node (ref "C133") (pin "1") (pinfunction "1_1") (pintype "passive"))
      (node (ref "FB3") (pin "2") (pinfunction "2_2") (pintype "passive"))
      (node (ref "U10") (pin "A2") (pinfunction "U3RXVDDQ_A2") (pintype "power_in"))
    )
    (net (code "91") (name "VCC1V2_USBTX") (class "Default")
      (node (ref "C138") (pin "1") (pinfunction "1_1") (pintype "passive"))
      (node (ref "C139") (pin "1") (pinfunction "1_1") (pintype "passive"))
      (node (ref "FB5") (pin "2") (pinfunction "2_2") (pintype "passive"))
      (node (ref "U10") (pin "B5") (pinfunction "U3TXVDDQ_B5") (pintype "power_in"))
    )
    (net (code "92") (name "VCC1V8") (class "Default")
      (node (ref "C140") (pin "1") (pinfunction "1_1") (pintype "passive"))
      (node (ref "C141") (pin "1") (pinfunction "1_1") (pintype "passive"))
      (node (ref "C142") (pin "1") (pinfunction "1_1") (pintype "passive"))
      (node (ref "C143") (pin "1") (pinfunction "1_1") (pintype "passive"))
      (node (ref "C144") (pin "1") (pinfunction "1_1") (pintype "passive"))
      (node (ref "C145") (pin "1") (pinfunction "1_1") (pintype "passive"))
      (node (ref "C146") (pin "1") (pinfunction "1_1") (pintype "passive"))
      (node (ref "C147") (pin "1") (pinfunction "1_1") (pintype "passive"))
      (node (ref "C148") (pin "1") (pinfunction "1_1") (pintype "passive"))
      (node (ref "C149") (pin "1") (pinfunction "1_1") (pintype "passive"))
      (node (ref "C150") (pin "1") (pinfunction "1_1") (pintype "passive"))
      (node (ref "C151") (pin "1") (pinfunction "1_1") (pintype "passive"))
      (node (ref "C155") (pin "1") (pinfunction "1_1") (pintype "passive"))
      (node (ref "FB2") (pin "1") (pinfunction "1_1") (pintype "passive"))
      (node (ref "R36") (pin "1") (pinfunction "1_1") (pintype "passive"))
      (node (ref "R37") (pin "1") (pinfunction "1_1") (pintype "passive"))
      (node (ref "R38") (pin "2") (pinfunction "2_2") (pintype "passive"))
      (node (ref "R39") (pin "2") (pinfunction "2_2") (pintype "passive"))
      (node (ref "R40") (pin "2") (pinfunction "2_2") (pintype "passive"))
      (node (ref "R41") (pin "2") (pinfunction "2_2") (pintype "passive"))
      (node (ref "U10") (pin "B1") (pinfunction "VIO4_B1") (pintype "power_in"))
      (node (ref "U10") (pin "C11") (pinfunction "VIO5_C11") (pintype "power_in"))
      (node (ref "U10") (pin "E3") (pinfunction "VIO3_E3") (pintype "power_in"))
      (node (ref "U10") (pin "F1") (pinfunction "VIO2_F1") (pintype "power_in"))
      (node (ref "U10") (pin "H11") (pinfunction "VIO1_H11") (pintype "power_in"))
      (node (ref "U10") (pin "L9") (pinfunction "VIO1_L9") (pintype "power_in"))
      (node (ref "U12") (pin "8") (pinfunction "VCC_8") (pintype "passive"))
    )
    (net (code "93") (name "VCC1V8_CVDDQ") (class "Default")
      (node (ref "C130") (pin "1") (pinfunction "1_1") (pintype "passive"))
      (node (ref "C131") (pin "1") (pinfunction "1_1") (pintype "passive"))
      (node (ref "FB2") (pin "2") (pinfunction "2_2") (pintype "passive"))
      (node (ref "U10") (pin "B6") (pinfunction "CVDDQ_B6") (pintype "power_in"))
    )
    (net (code "94") (name "unconnected-(P5-Pad7)") (class "Default")
      (node (ref "P5") (pin "7") (pinfunction "7_7") (pintype "passive+no_connect"))
    )
    (net (code "95") (name "unconnected-(U10A-U3VSSQ-PadA1)") (class "Default")
      (node (ref "U10") (pin "A1") (pinfunction "U3VSSQ_A1") (pintype "power_in"))
    )
    (net (code "96") (name "unconnected-(U10B-CLKIN-PadD7)") (class "Default")
      (node (ref "U10") (pin "D7") (pinfunction "CLKIN_D7") (pintype "input+no_connect"))
    )
    (net (code "97") (name "unconnected-(U10B-CLKIN_32-PadD6)") (class "Default")
      (node (ref "U10") (pin "D6") (pinfunction "CLKIN_32_D6") (pintype "input+no_connect"))
    )
    (net (code "98") (name "unconnected-(U10B-NC-PadA11)") (class "Default")
      (node (ref "U10") (pin "A11") (pinfunction "NC_A11") (pintype "passive+no_connect"))
    )
    (net (code "99") (name "unconnected-(U10C-O[60]-PadD11)") (class "Default")
      (node (ref "U10") (pin "D11") (pinfunction "O[60]_D11") (pintype "output+no_connect"))
    )
    (net (code "100") (name "unconnected-(U10F-GPIO[45]-PadF2)") (class "Default")
      (node (ref "U10") (pin "F2") (pinfunction "GPIO[45]_F2") (pintype "bidirectional+no_connect"))
    )
  )
)
